# Level_Shifter.net
KiCad netlist of a schematic drawn in Altium Designer
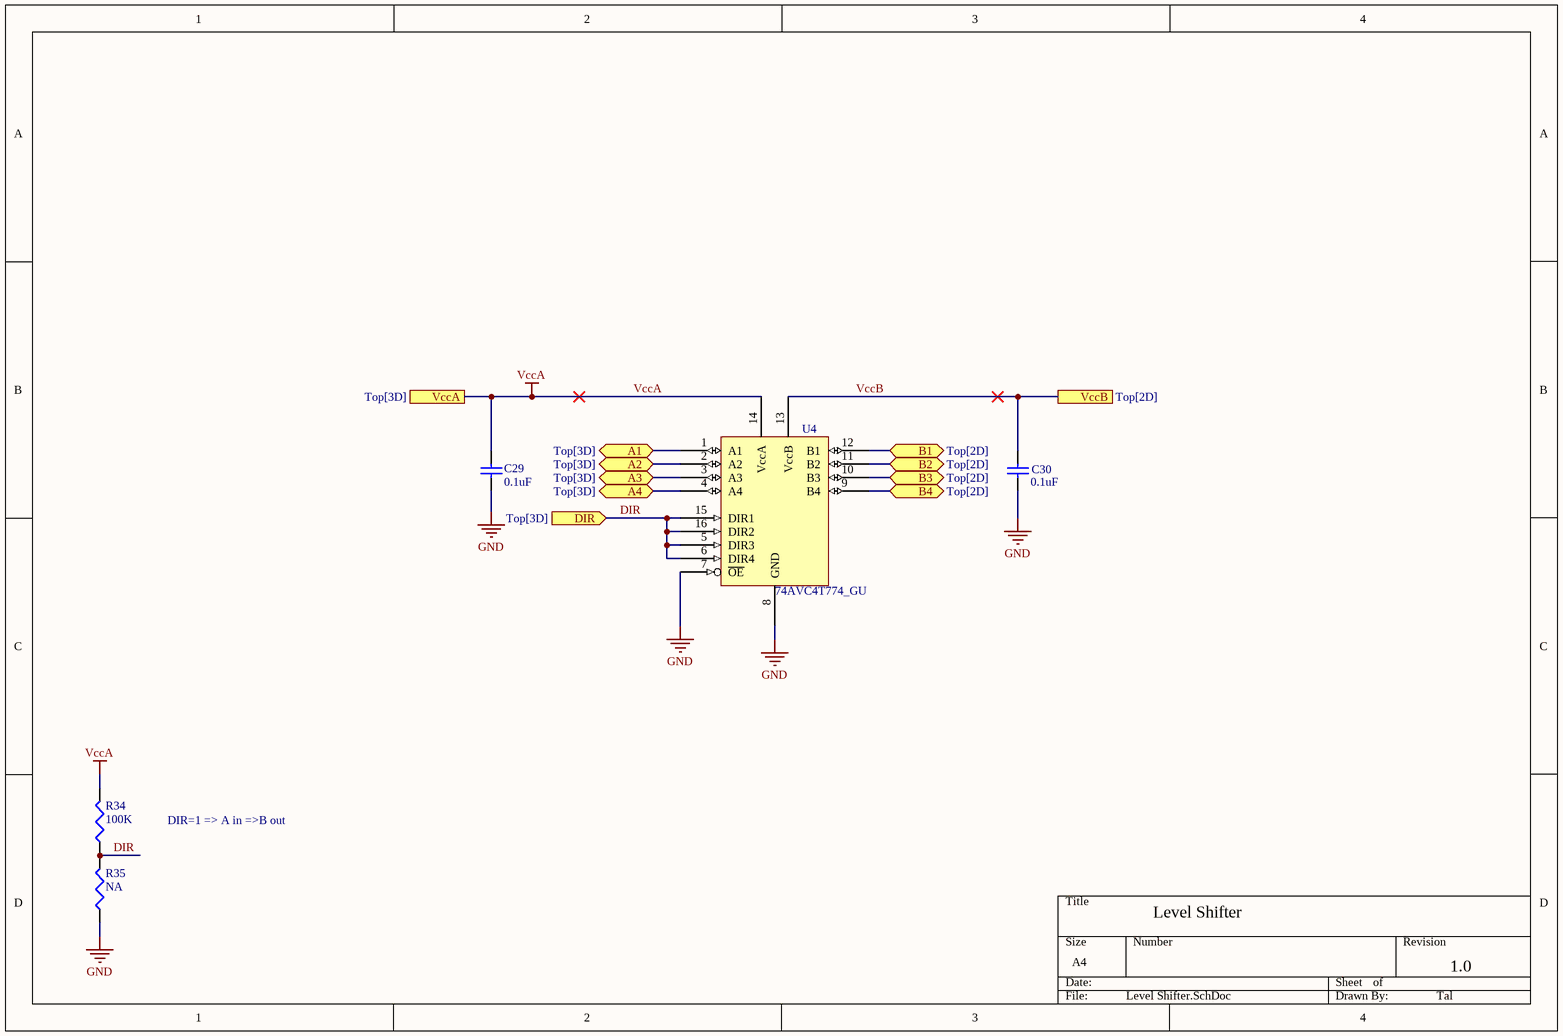
[diagram p0: Level Shifter.SchDoc]

(export (version "E")
  (design (tool "Eeschema 10.0.6"))
  (components
    (comp (ref "C29")
      (value "0.1uF 50V")
      (footprint "Landa_PCB:C0402")
      (description "CAP CER 0.1uF 50V NP0 0402")
      (fields
        (field (name "MANUFACTURER PART NUMBER") "C1005C0G1H6R8D")
        (field (name "MANUFACTURER") "TDK Corporation")
        (field (name "CAPACITANCE") "0.1uF")
      )
      (libsource (lib "L_SCH_C") (part "CAP CER 6.8pF 50V NP0 0402"))
    )
    (comp (ref "C30")
      (value "0.1uF 50V")
      (footprint "Landa_PCB:C0402")
      (description "CAP CER 0.1uF 50V NP0 0402")
      (fields
        (field (name "MANUFACTURER PART NUMBER") "C1005C0G1H6R8D")
        (field (name "MANUFACTURER") "TDK Corporation")
        (field (name "CAPACITANCE") "0.1uF")
      )
      (libsource (lib "L_SCH_C") (part "CAP CER 6.8pF 50V NP0 0402"))
    )
    (comp (ref "R34")
      (value "100K")
      (footprint "Landa_PCB:R0402")
      (description "RES 100K OHM 1/16W 1% 0402")
      (fields
        (field (name "MANUFACTURER PART NUMBER") "RMCF0402FT3K09")
        (field (name "MANUFACTURER") "Stackpole Electronics Inc")
      )
      (libsource (lib "L_SCH_R") (part "RES 3.09K OHM 1/16W 1% 0402"))
    )
    (comp (ref "R35")
      (value "NA")
      (footprint "Landa_PCB:R0402")
      (description "RES 3.09K OHM 1/16W 1% 0402")
      (fields
        (field (name "MANUFACTURER PART NUMBER") "RMCF0402FT3K09")
        (field (name "MANUFACTURER") "Stackpole Electronics Inc")
      )
      (libsource (lib "L_SCH_R") (part "RES 3.09K OHM 1/16W 1% 0402"))
    )
    (comp (ref "U4")
      (value "74AVC4T774_GU")
      (footprint "NXP_74AVC4T245GU,115")
      (libsource (lib "74AVC4T774_GU") (part "74AVC4T774_GU"))
    )
  )
  (nets
    (net (code "1") (name "/A1") (class "Default")
      (node (ref "U4") (pin "1") (pinfunction "A1_1") (pintype "bidirectional"))
    )
    (net (code "2") (name "/A2") (class "Default")
      (node (ref "U4") (pin "2") (pinfunction "A2_2") (pintype "bidirectional"))
    )
    (net (code "3") (name "/A3") (class "Default")
      (node (ref "U4") (pin "3") (pinfunction "A3_3") (pintype "bidirectional"))
    )
    (net (code "4") (name "/A4") (class "Default")
      (node (ref "U4") (pin "4") (pinfunction "A4_4") (pintype "bidirectional"))
    )
    (net (code "5") (name "/B1") (class "Default")
      (node (ref "U4") (pin "12") (pinfunction "B1_12") (pintype "bidirectional"))
    )
    (net (code "6") (name "/B2") (class "Default")
      (node (ref "U4") (pin "11") (pinfunction "B2_11") (pintype "bidirectional"))
    )
    (net (code "7") (name "/B3") (class "Default")
      (node (ref "U4") (pin "10") (pinfunction "B3_10") (pintype "bidirectional"))
    )
    (net (code "8") (name "/B4") (class "Default")
      (node (ref "U4") (pin "9") (pinfunction "B4_9") (pintype "bidirectional"))
    )
    (net (code "9") (name "/DIR") (class "Default")
      (node (ref "R34") (pin "1") (pinfunction "1_1") (pintype "passive"))
      (node (ref "R35") (pin "2") (pinfunction "2_2") (pintype "passive"))
      (node (ref "U4") (pin "15") (pinfunction "DIR1_15") (pintype "input"))
      (node (ref "U4") (pin "16") (pinfunction "DIR2_16") (pintype "input"))
      (node (ref "U4") (pin "5") (pinfunction "DIR3_5") (pintype "input"))
      (node (ref "U4") (pin "6") (pinfunction "DIR4_6") (pintype "input"))
    )
    (net (code "10") (name "/VccB") (class "Default")
      (node (ref "C30") (pin "2") (pinfunction "2_2") (pintype "passive"))
      (node (ref "U4") (pin "13") (pinfunction "VccB_13") (pintype "power_in"))
    )
    (net (code "11") (name "GND") (class "Default")
      (node (ref "C29") (pin "1") (pinfunction "1_1") (pintype "passive"))
      (node (ref "C30") (pin "1") (pinfunction "1_1") (pintype "passive"))
      (node (ref "R35") (pin "1") (pinfunction "1_1") (pintype "passive"))
      (node (ref "U4") (pin "7") (pinfunction "~{OE}_7") (pintype "input"))
      (node (ref "U4") (pin "8") (pinfunction "GND_8") (pintype "power_in"))
    )
    (net (code "12") (name "VccA") (class "Default")
      (node (ref "C29") (pin "2") (pinfunction "2_2") (pintype "passive"))
      (node (ref "R34") (pin "2") (pinfunction "2_2") (pintype "passive"))
      (node (ref "U4") (pin "14") (pinfunction "VccA_14") (pintype "power_in"))
    )
  )
)
